# VHF-Superregen-2-Transistor.net
KiCad netlist of a schematic drawn in EAGLE
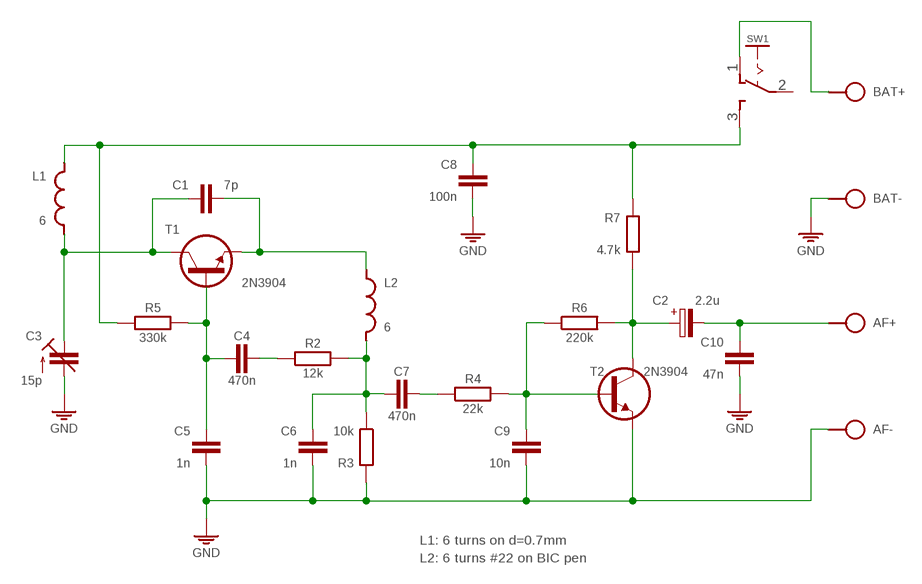
[diagram p0: schematic, sheet 1]

(export (version "E")
  (design (tool "Eeschema 10.0.6"))
  (components
    (comp (ref "AF+")
      (value "SPAD")
      (footprint "eagle-import:SPAD")
      (libsource (lib "eagle-import") (part "SPAD"))
    )
    (comp (ref "AF-")
      (value "SPAD")
      (footprint "eagle-import:SPAD")
      (libsource (lib "eagle-import") (part "SPAD"))
    )
    (comp (ref "BAT+")
      (value "SPAD")
      (footprint "eagle-import:SPAD")
      (libsource (lib "eagle-import") (part "SPAD"))
    )
    (comp (ref "BAT-")
      (value "SPAD")
      (footprint "eagle-import:SPAD")
      (libsource (lib "eagle-import") (part "SPAD"))
    )
    (comp (ref "C1")
      (value "7p")
      (footprint "eagle-import:C050-020X036")
      (libsource (lib "eagle-import") (part "C050-020X036"))
    )
    (comp (ref "C2")
      (value "2.2u")
      (footprint "eagle-import:E2,5-3")
      (libsource (lib "eagle-import") (part "CPOLE2,5-3"))
    )
    (comp (ref "C3")
      (value "15p")
      (footprint "eagle-import:TRIM-2222-808")
      (libsource (lib "eagle-import") (part "C-TR-PH201272222-808-2PINB"))
    )
    (comp (ref "C4")
      (value "470n")
      (footprint "eagle-import:C050-024X044_V")
      (libsource (lib "eagle-import") (part "C050-024X044/V"))
    )
    (comp (ref "C5")
      (value "1n")
      (footprint "eagle-import:C025-020X036")
      (libsource (lib "eagle-import") (part "C025-020X036"))
    )
    (comp (ref "C6")
      (value "1n")
      (footprint "eagle-import:C025-020X036")
      (libsource (lib "eagle-import") (part "C025-020X036"))
    )
    (comp (ref "C7")
      (value "470n")
      (footprint "eagle-import:C050-024X044_V")
      (libsource (lib "eagle-import") (part "C050-024X044/V"))
    )
    (comp (ref "C8")
      (value "100n")
      (footprint "eagle-import:C050-020X044_V")
      (libsource (lib "eagle-import") (part "C050-020X044/V"))
    )
    (comp (ref "C9")
      (value "10n")
      (footprint "eagle-import:C050-020X036_V")
      (libsource (lib "eagle-import") (part "C050-020X036/V"))
    )
    (comp (ref "C10")
      (value "47n")
      (footprint "eagle-import:C050-020X036")
      (libsource (lib "eagle-import") (part "C050-020X036"))
    )
    (comp (ref "L1")
      (value "6")
      (footprint "eagle-import:L-04_7V")
      (libsource (lib "eagle-import") (part "L-SHORTL-04/7V"))
    )
    (comp (ref "L2")
      (value "6")
      (footprint "eagle-import:L-04_7V")
      (libsource (lib "eagle-import") (part "L-SHORTL-04/7V"))
    )
    (comp (ref "R2")
      (value "12k")
      (footprint "eagle-import:0202_7-V")
      (libsource (lib "eagle-import") (part "R-H0202/7-V"))
    )
    (comp (ref "R3")
      (value "10k")
      (footprint "eagle-import:0202_7")
      (libsource (lib "eagle-import") (part "R0202/7"))
    )
    (comp (ref "R4")
      (value "22k")
      (footprint "eagle-import:0202_7-V")
      (libsource (lib "eagle-import") (part "R-H0202/7-V"))
    )
    (comp (ref "R5")
      (value "330k")
      (footprint "eagle-import:0202_7-V")
      (libsource (lib "eagle-import") (part "R-H0202/7-V"))
    )
    (comp (ref "R6")
      (value "220k")
      (footprint "eagle-import:0202_7-V")
      (libsource (lib "eagle-import") (part "R-H0202/7-V"))
    )
    (comp (ref "R7")
      (value "4.7k")
      (footprint "eagle-import:0202_7-V")
      (libsource (lib "eagle-import") (part "R0202/7-V"))
    )
    (comp (ref "SW1")
      (value "SL-SW-1P-2T-H")
      (footprint "eagle-import:SLSW-1P2T-H")
      (libsource (lib "eagle-import") (part "SL-SW-1P-2T-H"))
    )
    (comp (ref "T1")
      (value "2N3904")
      (footprint "eagle-import:TO92")
      (libsource (lib "eagle-import") (part "2N3904"))
    )
    (comp (ref "T2")
      (value "2N3904")
      (footprint "eagle-import:TO92")
      (libsource (lib "eagle-import") (part "2N3904"))
    )
  )
  (nets
    (net (code "1") (name "GND") (class "Default")
      (node (ref "AF-") (pin "1") (pinfunction "P$1_1") (pintype "bidirectional"))
      (node (ref "BAT-") (pin "1") (pinfunction "P$1_1") (pintype "bidirectional"))
      (node (ref "C10") (pin "2") (pinfunction "2_2") (pintype "passive"))
      (node (ref "C3") (pin "2") (pinfunction "A_2") (pintype "passive"))
      (node (ref "C5") (pin "2") (pinfunction "2_2") (pintype "passive"))
      (node (ref "C6") (pin "2") (pinfunction "2_2") (pintype "passive"))
      (node (ref "C8") (pin "2") (pinfunction "2_2") (pintype "passive"))
      (node (ref "C9") (pin "2") (pinfunction "2_2") (pintype "passive"))
      (node (ref "R3") (pin "2") (pinfunction "2_2") (pintype "passive"))
      (node (ref "T2") (pin "1") (pinfunction "E_1") (pintype "passive"))
    )
    (net (code "2") (name "Net-(AF+-P$1)") (class "Default")
      (node (ref "AF+") (pin "1") (pinfunction "P$1_1") (pintype "bidirectional"))
      (node (ref "C10") (pin "1") (pinfunction "1_1") (pintype "passive"))
      (node (ref "C2") (pin "-") (pinfunction "-_-") (pintype "passive"))
    )
    (net (code "3") (name "Net-(BAT+-P$1)") (class "Default")
      (node (ref "BAT+") (pin "1") (pinfunction "P$1_1") (pintype "bidirectional"))
      (node (ref "SW1") (pin "1") (pinfunction "O_1") (pintype "passive"))
    )
    (net (code "4") (name "Net-(C3-E)") (class "Default")
      (node (ref "C1") (pin "2") (pinfunction "2_2") (pintype "passive"))
      (node (ref "C3") (pin "3") (pinfunction "E_3") (pintype "passive"))
      (node (ref "L1") (pin "1") (pinfunction "1_1") (pintype "passive"))
      (node (ref "T1") (pin "3") (pinfunction "C_3") (pintype "passive"))
    )
    (net (code "5") (name "Net-(C4-Pad1)") (class "Default")
      (node (ref "C4") (pin "1") (pinfunction "1_1") (pintype "passive"))
      (node (ref "R2") (pin "1") (pinfunction "1_1") (pintype "passive"))
    )
    (net (code "6") (name "Net-(C6-Pad1)") (class "Default")
      (node (ref "C6") (pin "1") (pinfunction "1_1") (pintype "passive"))
      (node (ref "C7") (pin "2") (pinfunction "2_2") (pintype "passive"))
      (node (ref "L2") (pin "1") (pinfunction "1_1") (pintype "passive"))
      (node (ref "R2") (pin "2") (pinfunction "2_2") (pintype "passive"))
      (node (ref "R3") (pin "1") (pinfunction "1_1") (pintype "passive"))
    )
    (net (code "7") (name "Net-(C7-Pad1)") (class "Default")
      (node (ref "C7") (pin "1") (pinfunction "1_1") (pintype "passive"))
      (node (ref "R4") (pin "1") (pinfunction "1_1") (pintype "passive"))
    )
    (net (code "8") (name "Net-(SW1-S)") (class "Default")
      (node (ref "C8") (pin "1") (pinfunction "1_1") (pintype "passive"))
      (node (ref "L1") (pin "2") (pinfunction "2_2") (pintype "passive"))
      (node (ref "R5") (pin "1") (pinfunction "1_1") (pintype "passive"))
      (node (ref "R7") (pin "2") (pinfunction "2_2") (pintype "passive"))
      (node (ref "SW1") (pin "3") (pinfunction "S_3") (pintype "passive"))
    )
    (net (code "9") (name "Net-(T1-B)") (class "Default")
      (node (ref "C4") (pin "2") (pinfunction "2_2") (pintype "passive"))
      (node (ref "C5") (pin "1") (pinfunction "1_1") (pintype "passive"))
      (node (ref "R5") (pin "2") (pinfunction "2_2") (pintype "passive"))
      (node (ref "T1") (pin "2") (pinfunction "B_2") (pintype "passive"))
    )
    (net (code "10") (name "Net-(T1-E)") (class "Default")
      (node (ref "C1") (pin "1") (pinfunction "1_1") (pintype "passive"))
      (node (ref "L2") (pin "2") (pinfunction "2_2") (pintype "passive"))
      (node (ref "T1") (pin "1") (pinfunction "E_1") (pintype "passive"))
    )
    (net (code "11") (name "Net-(T2-B)") (class "Default")
      (node (ref "C9") (pin "1") (pinfunction "1_1") (pintype "passive"))
      (node (ref "R4") (pin "2") (pinfunction "2_2") (pintype "passive"))
      (node (ref "R6") (pin "1") (pinfunction "1_1") (pintype "passive"))
      (node (ref "T2") (pin "2") (pinfunction "B_2") (pintype "passive"))
    )
    (net (code "12") (name "Net-(T2-C)") (class "Default")
      (node (ref "C2") (pin "+") (pinfunction "+_+") (pintype "passive"))
      (node (ref "R6") (pin "2") (pinfunction "2_2") (pintype "passive"))
      (node (ref "R7") (pin "1") (pinfunction "1_1") (pintype "passive"))
      (node (ref "T2") (pin "3") (pinfunction "C_3") (pintype "passive"))
    )
    (net (code "13") (name "unconnected-(SW1-P-Pad2)") (class "Default")
      (node (ref "SW1") (pin "2") (pinfunction "P_2") (pintype "passive"))
    )
  )
)
